# sheet4_sk6812.net
KiCad netlist of a schematic drawn in Altium Designer
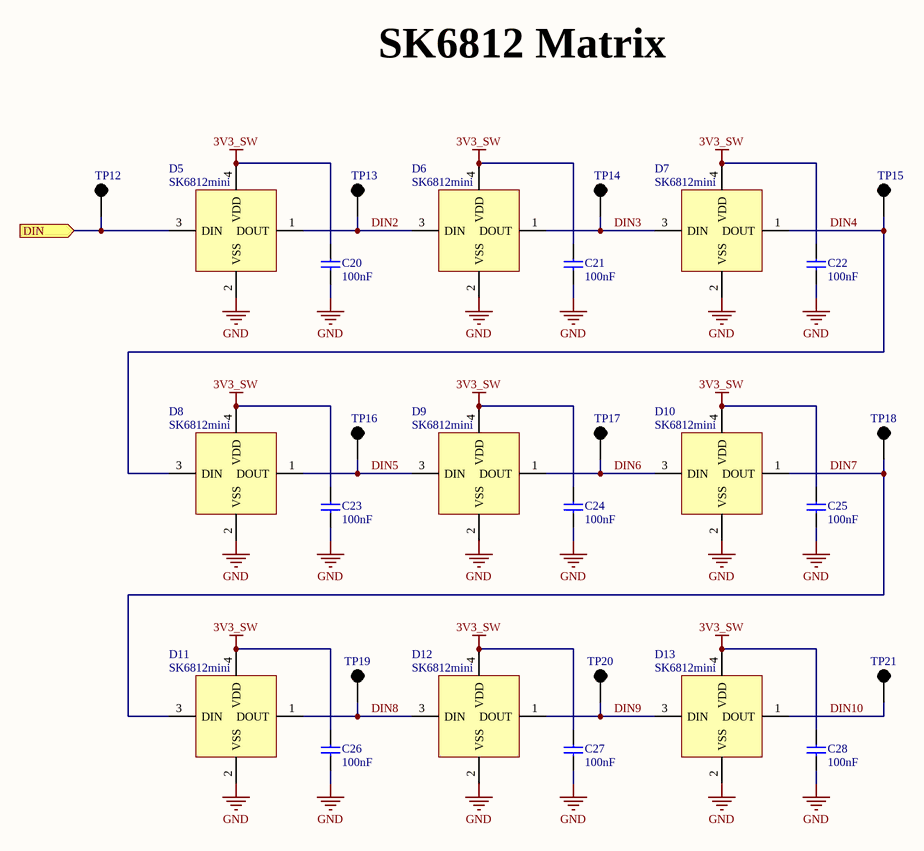
[diagram p0: sheet4_sk6812.SchDoc]

(export (version "E")
  (design (tool "Eeschema 10.0.6"))
  (components
    (comp (ref "C20")
      (value "100nF")
      (footprint "CAP0603_GCx18_MURATA")
      (description "Capacitor 0603 100nF")
      (fields
        (field (name "MANUFACTURER") "Murata")
        (field (name "MANUFACTURER PART NUMBER") "GCJ188R71C104KA01D")
      )
      (libsource (lib "Schlib") (part "CAP_0603_100nF"))
    )
    (comp (ref "C21")
      (value "100nF")
      (footprint "CAP0603_GCx18_MURATA")
      (description "Capacitor 0603 100nF")
      (fields
        (field (name "MANUFACTURER") "Murata")
        (field (name "MANUFACTURER PART NUMBER") "GCJ188R71C104KA01D")
      )
      (libsource (lib "Schlib") (part "CAP_0603_100nF"))
    )
    (comp (ref "C22")
      (value "100nF")
      (footprint "CAP0603_GCx18_MURATA")
      (description "Capacitor 0603 100nF")
      (fields
        (field (name "MANUFACTURER") "Murata")
        (field (name "MANUFACTURER PART NUMBER") "GCJ188R71C104KA01D")
      )
      (libsource (lib "Schlib") (part "CAP_0603_100nF"))
    )
    (comp (ref "C23")
      (value "100nF")
      (footprint "CAP0603_GCx18_MURATA")
      (description "Capacitor 0603 100nF")
      (fields
        (field (name "MANUFACTURER") "Murata")
        (field (name "MANUFACTURER PART NUMBER") "GCJ188R71C104KA01D")
      )
      (libsource (lib "Schlib") (part "CAP_0603_100nF"))
    )
    (comp (ref "C24")
      (value "100nF")
      (footprint "CAP0603_GCx18_MURATA")
      (description "Capacitor 0603 100nF")
      (fields
        (field (name "MANUFACTURER") "Murata")
        (field (name "MANUFACTURER PART NUMBER") "GCJ188R71C104KA01D")
      )
      (libsource (lib "Schlib") (part "CAP_0603_100nF"))
    )
    (comp (ref "C25")
      (value "100nF")
      (footprint "CAP0603_GCx18_MURATA")
      (description "Capacitor 0603 100nF")
      (fields
        (field (name "MANUFACTURER") "Murata")
        (field (name "MANUFACTURER PART NUMBER") "GCJ188R71C104KA01D")
      )
      (libsource (lib "Schlib") (part "CAP_0603_100nF"))
    )
    (comp (ref "C26")
      (value "100nF")
      (footprint "CAP0603_GCx18_MURATA")
      (description "Capacitor 0603 100nF")
      (fields
        (field (name "MANUFACTURER") "Murata")
        (field (name "MANUFACTURER PART NUMBER") "GCJ188R71C104KA01D")
      )
      (libsource (lib "Schlib") (part "CAP_0603_100nF"))
    )
    (comp (ref "C27")
      (value "100nF")
      (footprint "CAP0603_GCx18_MURATA")
      (description "Capacitor 0603 100nF")
      (fields
        (field (name "MANUFACTURER") "Murata")
        (field (name "MANUFACTURER PART NUMBER") "GCJ188R71C104KA01D")
      )
      (libsource (lib "Schlib") (part "CAP_0603_100nF"))
    )
    (comp (ref "C28")
      (value "100nF")
      (footprint "CAP0603_GCx18_MURATA")
      (description "Capacitor 0603 100nF")
      (fields
        (field (name "MANUFACTURER") "Murata")
        (field (name "MANUFACTURER PART NUMBER") "GCJ188R71C104KA01D")
      )
      (libsource (lib "Schlib") (part "CAP_0603_100nF"))
    )
    (comp (ref "D5")
      (value "SK6812mini")
      (footprint "SK6812mini")
      (description "RGB LED with integrated controller")
      (fields (field (name "MANUFACTURER") "Dongguang opsco optoelectronics CO. LTD"))
      (libsource (lib "Schlib") (part "SK6812"))
    )
    (comp (ref "D6")
      (value "SK6812mini")
      (footprint "SK6812mini")
      (description "RGB LED with integrated controller")
      (fields (field (name "MANUFACTURER") "Dongguang opsco optoelectronics CO. LTD"))
      (libsource (lib "Schlib") (part "SK6812"))
    )
    (comp (ref "D7")
      (value "SK6812mini")
      (footprint "SK6812mini")
      (description "RGB LED with integrated controller")
      (fields (field (name "MANUFACTURER") "Dongguang opsco optoelectronics CO. LTD"))
      (libsource (lib "Schlib") (part "SK6812"))
    )
    (comp (ref "D8")
      (value "SK6812mini")
      (footprint "SK6812mini")
      (description "RGB LED with integrated controller")
      (fields (field (name "MANUFACTURER") "Dongguang opsco optoelectronics CO. LTD"))
      (libsource (lib "Schlib") (part "SK6812"))
    )
    (comp (ref "D9")
      (value "SK6812mini")
      (footprint "SK6812mini")
      (description "RGB LED with integrated controller")
      (fields (field (name "MANUFACTURER") "Dongguang opsco optoelectronics CO. LTD"))
      (libsource (lib "Schlib") (part "SK6812"))
    )
    (comp (ref "D10")
      (value "SK6812mini")
      (footprint "SK6812mini")
      (description "RGB LED with integrated controller")
      (fields (field (name "MANUFACTURER") "Dongguang opsco optoelectronics CO. LTD"))
      (libsource (lib "Schlib") (part "SK6812"))
    )
    (comp (ref "D11")
      (value "SK6812mini")
      (footprint "SK6812mini")
      (description "RGB LED with integrated controller")
      (fields (field (name "MANUFACTURER") "Dongguang opsco optoelectronics CO. LTD"))
      (libsource (lib "Schlib") (part "SK6812"))
    )
    (comp (ref "D12")
      (value "SK6812mini")
      (footprint "SK6812mini")
      (description "RGB LED with integrated controller")
      (fields (field (name "MANUFACTURER") "Dongguang opsco optoelectronics CO. LTD"))
      (libsource (lib "Schlib") (part "SK6812"))
    )
    (comp (ref "D13")
      (value "SK6812mini")
      (footprint "SK6812mini")
      (description "RGB LED with integrated controller")
      (fields (field (name "MANUFACTURER") "Dongguang opsco optoelectronics CO. LTD"))
      (libsource (lib "Schlib") (part "SK6812"))
    )
    (comp (ref "TP12")
      (value "testpad")
      (footprint "TestPad")
      (description "Signal probe pad")
      (libsource (lib "Schlib") (part "TestPad"))
    )
    (comp (ref "TP13")
      (value "testpad")
      (footprint "TestPad")
      (description "Signal probe pad")
      (libsource (lib "Schlib") (part "TestPad"))
    )
    (comp (ref "TP14")
      (value "testpad")
      (footprint "TestPad")
      (description "Signal probe pad")
      (libsource (lib "Schlib") (part "TestPad"))
    )
    (comp (ref "TP15")
      (value "testpad")
      (footprint "TestPad")
      (description "Signal probe pad")
      (libsource (lib "Schlib") (part "TestPad"))
    )
    (comp (ref "TP16")
      (value "testpad")
      (footprint "TestPad")
      (description "Signal probe pad")
      (libsource (lib "Schlib") (part "TestPad"))
    )
    (comp (ref "TP17")
      (value "testpad")
      (footprint "TestPad")
      (description "Signal probe pad")
      (libsource (lib "Schlib") (part "TestPad"))
    )
    (comp (ref "TP18")
      (value "testpad")
      (footprint "TestPad")
      (description "Signal probe pad")
      (libsource (lib "Schlib") (part "TestPad"))
    )
    (comp (ref "TP19")
      (value "testpad")
      (footprint "TestPad")
      (description "Signal probe pad")
      (libsource (lib "Schlib") (part "TestPad"))
    )
    (comp (ref "TP20")
      (value "testpad")
      (footprint "TestPad")
      (description "Signal probe pad")
      (libsource (lib "Schlib") (part "TestPad"))
    )
    (comp (ref "TP21")
      (value "testpad")
      (footprint "TestPad")
      (description "Signal probe pad")
      (libsource (lib "Schlib") (part "TestPad"))
    )
  )
  (nets
    (net (code "1") (name "/DIN") (class "Default")
      (node (ref "D5") (pin "3") (pinfunction "DIN_3") (pintype "passive"))
      (node (ref "TP12") (pin "1") (pinfunction "1_1") (pintype "passive"))
    )
    (net (code "2") (name "/DIN2") (class "Default")
      (node (ref "D5") (pin "1") (pinfunction "DOUT_1") (pintype "passive"))
      (node (ref "D6") (pin "3") (pinfunction "DIN_3") (pintype "passive"))
      (node (ref "TP13") (pin "1") (pinfunction "1_1") (pintype "passive"))
    )
    (net (code "3") (name "/DIN3") (class "Default")
      (node (ref "D6") (pin "1") (pinfunction "DOUT_1") (pintype "passive"))
      (node (ref "D7") (pin "3") (pinfunction "DIN_3") (pintype "passive"))
      (node (ref "TP14") (pin "1") (pinfunction "1_1") (pintype "passive"))
    )
    (net (code "4") (name "/DIN4") (class "Default")
      (node (ref "D7") (pin "1") (pinfunction "DOUT_1") (pintype "passive"))
      (node (ref "D8") (pin "3") (pinfunction "DIN_3") (pintype "passive"))
      (node (ref "TP15") (pin "1") (pinfunction "1_1") (pintype "passive"))
    )
    (net (code "5") (name "/DIN5") (class "Default")
      (node (ref "D8") (pin "1") (pinfunction "DOUT_1") (pintype "passive"))
      (node (ref "D9") (pin "3") (pinfunction "DIN_3") (pintype "passive"))
      (node (ref "TP16") (pin "1") (pinfunction "1_1") (pintype "passive"))
    )
    (net (code "6") (name "/DIN6") (class "Default")
      (node (ref "D10") (pin "3") (pinfunction "DIN_3") (pintype "passive"))
      (node (ref "D9") (pin "1") (pinfunction "DOUT_1") (pintype "passive"))
      (node (ref "TP17") (pin "1") (pinfunction "1_1") (pintype "passive"))
    )
    (net (code "7") (name "/DIN7") (class "Default")
      (node (ref "D10") (pin "1") (pinfunction "DOUT_1") (pintype "passive"))
      (node (ref "D11") (pin "3") (pinfunction "DIN_3") (pintype "passive"))
      (node (ref "TP18") (pin "1") (pinfunction "1_1") (pintype "passive"))
    )
    (net (code "8") (name "/DIN8") (class "Default")
      (node (ref "D11") (pin "1") (pinfunction "DOUT_1") (pintype "passive"))
      (node (ref "D12") (pin "3") (pinfunction "DIN_3") (pintype "passive"))
      (node (ref "TP19") (pin "1") (pinfunction "1_1") (pintype "passive"))
    )
    (net (code "9") (name "/DIN9") (class "Default")
      (node (ref "D12") (pin "1") (pinfunction "DOUT_1") (pintype "passive"))
      (node (ref "D13") (pin "3") (pinfunction "DIN_3") (pintype "passive"))
      (node (ref "TP20") (pin "1") (pinfunction "1_1") (pintype "passive"))
    )
    (net (code "10") (name "/DIN10") (class "Default")
      (node (ref "D13") (pin "1") (pinfunction "DOUT_1") (pintype "passive"))
      (node (ref "TP21") (pin "1") (pinfunction "1_1") (pintype "passive"))
    )
    (net (code "11") (name "3V3_SW") (class "Default")
      (node (ref "C20") (pin "2") (pinfunction "2_2") (pintype "passive"))
      (node (ref "C21") (pin "2") (pinfunction "2_2") (pintype "passive"))
      (node (ref "C22") (pin "2") (pinfunction "2_2") (pintype "passive"))
      (node (ref "C23") (pin "2") (pinfunction "2_2") (pintype "passive"))
      (node (ref "C24") (pin "2") (pinfunction "2_2") (pintype "passive"))
      (node (ref "C25") (pin "2") (pinfunction "2_2") (pintype "passive"))
      (node (ref "C26") (pin "2") (pinfunction "2_2") (pintype "passive"))
      (node (ref "C27") (pin "2") (pinfunction "2_2") (pintype "passive"))
      (node (ref "C28") (pin "2") (pinfunction "2_2") (pintype "passive"))
      (node (ref "D10") (pin "4") (pinfunction "VDD_4") (pintype "passive"))
      (node (ref "D11") (pin "4") (pinfunction "VDD_4") (pintype "passive"))
      (node (ref "D12") (pin "4") (pinfunction "VDD_4") (pintype "passive"))
      (node (ref "D13") (pin "4") (pinfunction "VDD_4") (pintype "passive"))
      (node (ref "D5") (pin "4") (pinfunction "VDD_4") (pintype "passive"))
      (node (ref "D6") (pin "4") (pinfunction "VDD_4") (pintype "passive"))
      (node (ref "D7") (pin "4") (pinfunction "VDD_4") (pintype "passive"))
      (node (ref "D8") (pin "4") (pinfunction "VDD_4") (pintype "passive"))
      (node (ref "D9") (pin "4") (pinfunction "VDD_4") (pintype "passive"))
    )
    (net (code "12") (name "GND") (class "Default")
      (node (ref "C20") (pin "1") (pinfunction "1_1") (pintype "passive"))
      (node (ref "C21") (pin "1") (pinfunction "1_1") (pintype "passive"))
      (node (ref "C22") (pin "1") (pinfunction "1_1") (pintype "passive"))
      (node (ref "C23") (pin "1") (pinfunction "1_1") (pintype "passive"))
      (node (ref "C24") (pin "1") (pinfunction "1_1") (pintype "passive"))
      (node (ref "C25") (pin "1") (pinfunction "1_1") (pintype "passive"))
      (node (ref "C26") (pin "1") (pinfunction "1_1") (pintype "passive"))
      (node (ref "C27") (pin "1") (pinfunction "1_1") (pintype "passive"))
      (node (ref "C28") (pin "1") (pinfunction "1_1") (pintype "passive"))
      (node (ref "D10") (pin "2") (pinfunction "VSS_2") (pintype "passive"))
      (node (ref "D11") (pin "2") (pinfunction "VSS_2") (pintype "passive"))
      (node (ref "D12") (pin "2") (pinfunction "VSS_2") (pintype "passive"))
      (node (ref "D13") (pin "2") (pinfunction "VSS_2") (pintype "passive"))
      (node (ref "D5") (pin "2") (pinfunction "VSS_2") (pintype "passive"))
      (node (ref "D6") (pin "2") (pinfunction "VSS_2") (pintype "passive"))
      (node (ref "D7") (pin "2") (pinfunction "VSS_2") (pintype "passive"))
      (node (ref "D8") (pin "2") (pinfunction "VSS_2") (pintype "passive"))
      (node (ref "D9") (pin "2") (pinfunction "VSS_2") (pintype "passive"))
    )
  )
)
